# Mechanical.net
KiCad netlist of a schematic drawn in Altium Designer
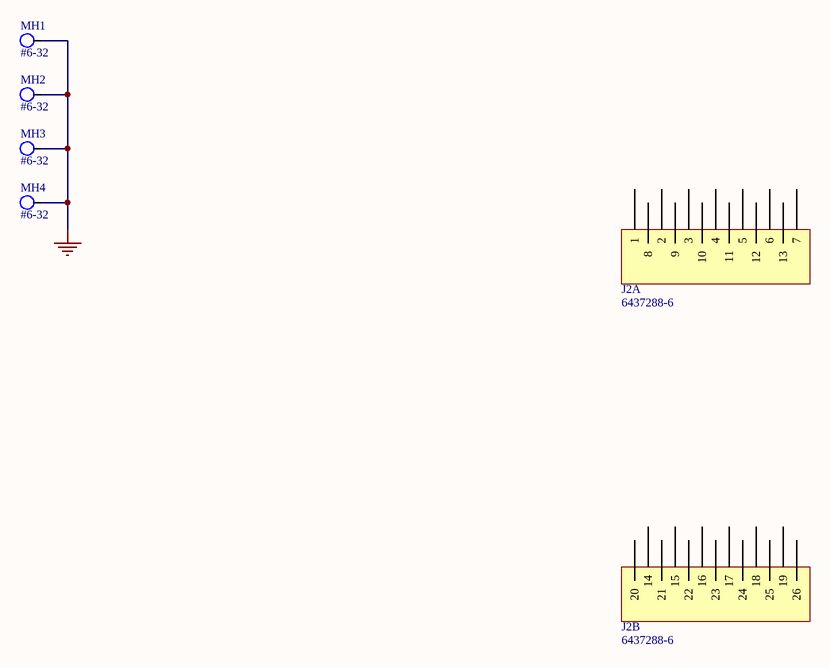
[diagram p0: Mechanical.SchDoc]

(export (version "E")
  (design (tool "Eeschema 10.0.6"))
  (components
    (comp (ref "J2")
      (value "6437288-6")
      (footprint "6437288-6")
      (description "Superseal 26-way vertical PCB header")
      (libsource (lib "Connectors") (part "6437288-6"))
    )
    (comp (ref "MH1") (value "#6-32") (footprint "MH-6-32") (libsource (lib "Hub-UV17") (part "MH-6-32")))
    (comp (ref "MH2") (value "#6-32") (footprint "MH-6-32") (libsource (lib "Hub-UV17") (part "MH-6-32")))
    (comp (ref "MH3") (value "#6-32") (footprint "MH-6-32") (libsource (lib "Hub-UV17") (part "MH-6-32")))
    (comp (ref "MH4") (value "#6-32") (footprint "MH-6-32") (libsource (lib "Hub-UV17") (part "MH-6-32")))
  )
  (nets
    (net (code "1") (name "GND") (class "Default")
      (node (ref "MH1") (pin "1") (pinfunction "1_1") (pintype "passive"))
      (node (ref "MH2") (pin "1") (pinfunction "1_1") (pintype "passive"))
      (node (ref "MH3") (pin "1") (pinfunction "1_1") (pintype "passive"))
      (node (ref "MH4") (pin "1") (pinfunction "1_1") (pintype "passive"))
    )
    (net (code "2") (name "unconnected-(J2-Pad1)") (class "Default")
      (node (ref "J2") (pin "1") (pinfunction "1_1") (pintype "passive"))
    )
    (net (code "3") (name "unconnected-(J2-Pad2)") (class "Default")
      (node (ref "J2") (pin "2") (pinfunction "2_2") (pintype "passive"))
    )
    (net (code "4") (name "unconnected-(J2-Pad3)") (class "Default")
      (node (ref "J2") (pin "3") (pinfunction "3_3") (pintype "passive"))
    )
    (net (code "5") (name "unconnected-(J2-Pad4)") (class "Default")
      (node (ref "J2") (pin "4") (pinfunction "4_4") (pintype "passive"))
    )
    (net (code "6") (name "unconnected-(J2-Pad5)") (class "Default")
      (node (ref "J2") (pin "5") (pinfunction "5_5") (pintype "passive"))
    )
    (net (code "7") (name "unconnected-(J2-Pad6)") (class "Default")
      (node (ref "J2") (pin "6") (pinfunction "6_6") (pintype "passive"))
    )
    (net (code "8") (name "unconnected-(J2-Pad7)") (class "Default")
      (node (ref "J2") (pin "7") (pinfunction "7_7") (pintype "passive"))
    )
    (net (code "9") (name "unconnected-(J2-Pad8)") (class "Default")
      (node (ref "J2") (pin "8") (pinfunction "8_8") (pintype "passive"))
    )
    (net (code "10") (name "unconnected-(J2-Pad9)") (class "Default")
      (node (ref "J2") (pin "9") (pinfunction "9_9") (pintype "passive"))
    )
    (net (code "11") (name "unconnected-(J2-Pad10)") (class "Default")
      (node (ref "J2") (pin "10") (pinfunction "10_10") (pintype "passive"))
    )
    (net (code "12") (name "unconnected-(J2-Pad11)") (class "Default")
      (node (ref "J2") (pin "11") (pinfunction "11_11") (pintype "passive"))
    )
    (net (code "13") (name "unconnected-(J2-Pad12)") (class "Default")
      (node (ref "J2") (pin "12") (pinfunction "12_12") (pintype "passive"))
    )
    (net (code "14") (name "unconnected-(J2-Pad13)") (class "Default")
      (node (ref "J2") (pin "13") (pinfunction "13_13") (pintype "passive"))
    )
    (net (code "15") (name "unconnected-(J2-Pad14)") (class "Default")
      (node (ref "J2") (pin "14") (pinfunction "14_14") (pintype "passive"))
    )
    (net (code "16") (name "unconnected-(J2-Pad15)") (class "Default")
      (node (ref "J2") (pin "15") (pinfunction "15_15") (pintype "passive"))
    )
    (net (code "17") (name "unconnected-(J2-Pad16)") (class "Default")
      (node (ref "J2") (pin "16") (pinfunction "16_16") (pintype "passive"))
    )
    (net (code "18") (name "unconnected-(J2-Pad17)") (class "Default")
      (node (ref "J2") (pin "17") (pinfunction "17_17") (pintype "passive"))
    )
    (net (code "19") (name "unconnected-(J2-Pad18)") (class "Default")
      (node (ref "J2") (pin "18") (pinfunction "18_18") (pintype "passive"))
    )
    (net (code "20") (name "unconnected-(J2-Pad19)") (class "Default")
      (node (ref "J2") (pin "19") (pinfunction "19_19") (pintype "passive"))
    )
    (net (code "21") (name "unconnected-(J2-Pad20)") (class "Default")
      (node (ref "J2") (pin "20") (pinfunction "20_20") (pintype "passive"))
    )
    (net (code "22") (name "unconnected-(J2-Pad21)") (class "Default")
      (node (ref "J2") (pin "21") (pinfunction "21_21") (pintype "passive"))
    )
    (net (code "23") (name "unconnected-(J2-Pad22)") (class "Default")
      (node (ref "J2") (pin "22") (pinfunction "22_22") (pintype "passive"))
    )
    (net (code "24") (name "unconnected-(J2-Pad23)") (class "Default")
      (node (ref "J2") (pin "23") (pinfunction "23_23") (pintype "passive"))
    )
    (net (code "25") (name "unconnected-(J2-Pad24)") (class "Default")
      (node (ref "J2") (pin "24") (pinfunction "24_24") (pintype "passive"))
    )
    (net (code "26") (name "unconnected-(J2-Pad25)") (class "Default")
      (node (ref "J2") (pin "25") (pinfunction "25_25") (pintype "passive"))
    )
    (net (code "27") (name "unconnected-(J2-Pad26)") (class "Default")
      (node (ref "J2") (pin "26") (pinfunction "26_26") (pintype "passive"))
    )
  )
)
